# ASIC-Board.net
KiCad netlist of a schematic drawn in Altium Designer
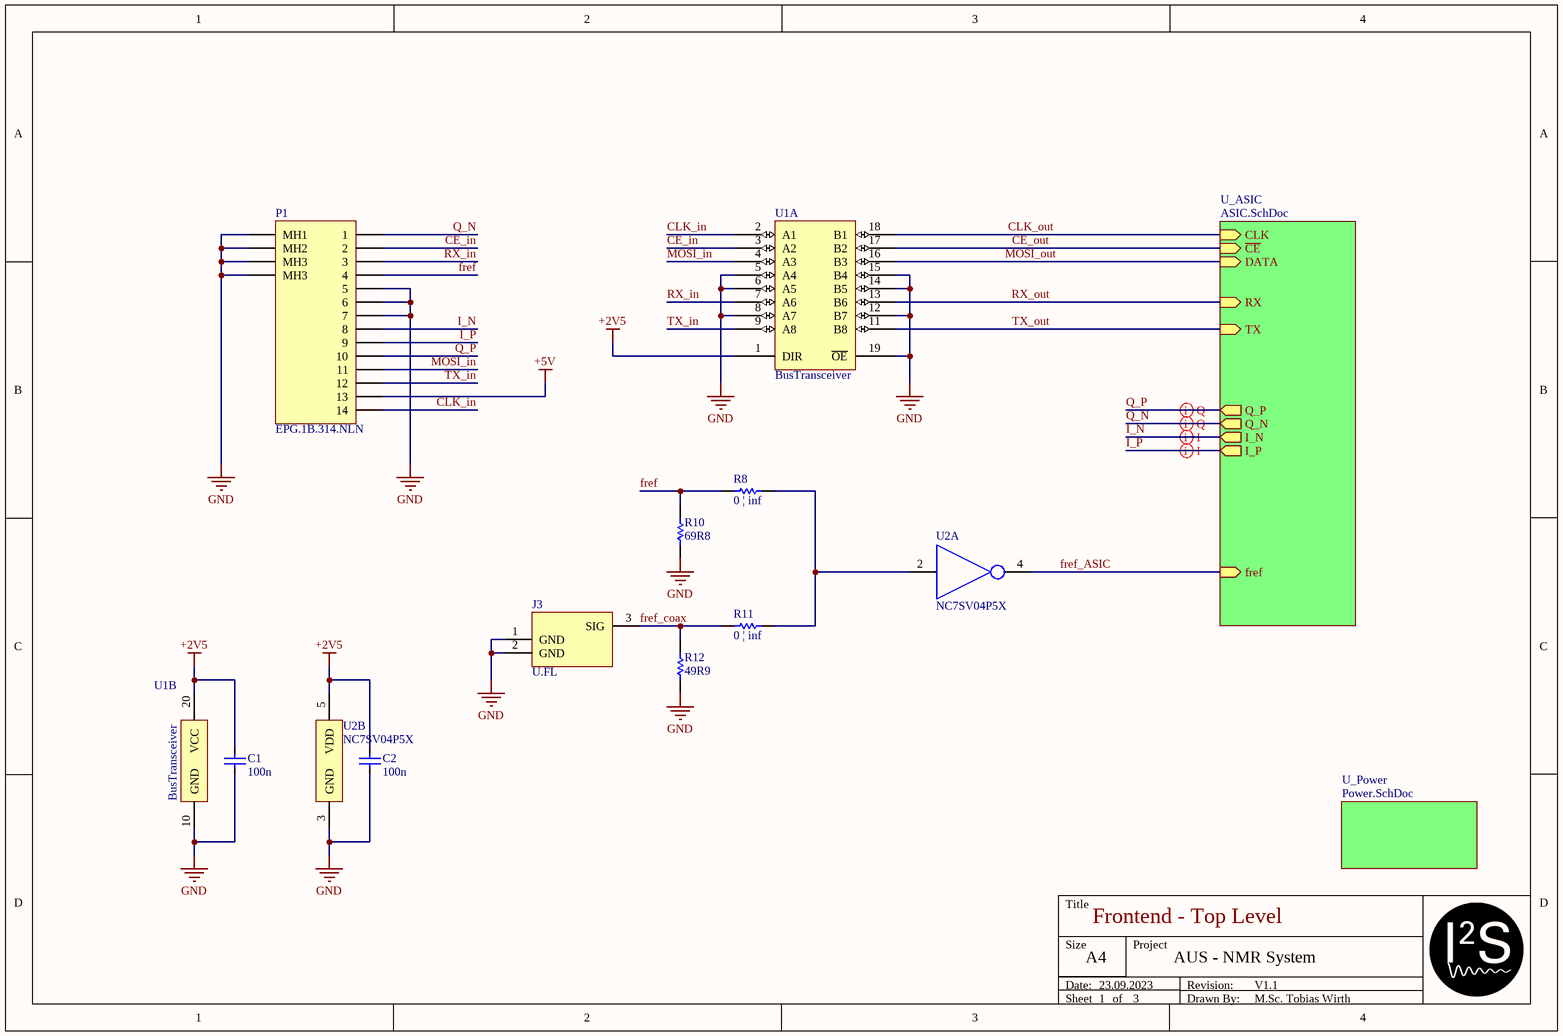
[diagram p0: ASIC-Board.SchDoc]

(export (version "E")
  (design (tool "Eeschema 10.0.6"))
  (components
    (comp (ref "C1") (value "100n") (footprint "CAP_0402") (libsource (lib "IIS-Lib_TW") (part "Cap")))
    (comp (ref "C2") (value "100n") (footprint "CAP_0402") (libsource (lib "IIS-Lib_TW") (part "Cap")))
    (comp (ref "J3") (value "U.FL") (footprint "U.FL") (libsource (lib "IIS-Lib_TW") (part "U.FL")))
    (comp (ref "P1")
      (value "EPG.1B.314.NLN")
      (footprint "EPG.1B.314.NLN")
      (libsource (lib "IIS-Lib_TW") (part "EPG.1B.314.NLN"))
    )
    (comp (ref "R8") (value "0 ¦ inf") (footprint "RES_0402") (libsource (lib "IIS-Lib_TW") (part "Res")))
    (comp (ref "R10") (value "69R8") (footprint "RES_0402") (libsource (lib "IIS-Lib_TW") (part "Res")))
    (comp (ref "R11") (value "0 ¦ inf") (footprint "RES_0402") (libsource (lib "IIS-Lib_TW") (part "Res")))
    (comp (ref "R12") (value "49R9") (footprint "RES_0402") (libsource (lib "IIS-Lib_TW") (part "Res")))
    (comp (ref "U1")
      (value "BusTransceiver")
      (footprint "TSSOP-20")
      (libsource (lib "IIS-Lib_TW") (part "74LVC245A"))
    )
    (comp (ref "U2")
      (value "NC7SV04P5X")
      (footprint "SOT23-65P210X110-5N")
      (libsource (lib "IIS-Lib_TW") (part "NC7SV04P5X"))
    )
  )
  (nets
    (net (code "1") (name "+2V5") (class "Default")
      (node (ref "C1") (pin "1") (pinfunction "1_1") (pintype "passive"))
      (node (ref "C2") (pin "1") (pinfunction "1_1") (pintype "passive"))
      (node (ref "U1") (pin "1") (pinfunction "DIR_1") (pintype "passive"))
      (node (ref "U1") (pin "20") (pinfunction "VCC_20") (pintype "passive"))
      (node (ref "U2") (pin "5") (pinfunction "VDD_5") (pintype "passive"))
    )
    (net (code "2") (name "+5V") (class "Default")
      (node (ref "P1") (pin "13") (pinfunction "13_13") (pintype "passive"))
    )
    (net (code "3") (name "/CE_in") (class "Default")
      (node (ref "P1") (pin "2") (pinfunction "2_2") (pintype "passive"))
      (node (ref "U1") (pin "3") (pinfunction "A2_3") (pintype "bidirectional"))
    )
    (net (code "4") (name "/CE_out") (class "Default")
      (node (ref "U1") (pin "17") (pinfunction "B2_17") (pintype "bidirectional"))
    )
    (net (code "5") (name "/CLK_in") (class "Default")
      (node (ref "P1") (pin "14") (pinfunction "14_14") (pintype "passive"))
      (node (ref "U1") (pin "2") (pinfunction "A1_2") (pintype "bidirectional"))
    )
    (net (code "6") (name "/CLK_out") (class "Default")
      (node (ref "U1") (pin "18") (pinfunction "B1_18") (pintype "bidirectional"))
    )
    (net (code "7") (name "/I_N") (class "Default")
      (node (ref "P1") (pin "8") (pinfunction "8_8") (pintype "passive"))
    )
    (net (code "8") (name "/I_P") (class "Default")
      (node (ref "P1") (pin "9") (pinfunction "9_9") (pintype "passive"))
    )
    (net (code "9") (name "/MOSI_in") (class "Default")
      (node (ref "P1") (pin "11") (pinfunction "11_11") (pintype "passive"))
      (node (ref "U1") (pin "4") (pinfunction "A3_4") (pintype "bidirectional"))
    )
    (net (code "10") (name "/MOSI_out") (class "Default")
      (node (ref "U1") (pin "16") (pinfunction "B3_16") (pintype "bidirectional"))
    )
    (net (code "11") (name "/Q_N") (class "Default")
      (node (ref "P1") (pin "1") (pinfunction "1_1") (pintype "passive"))
    )
    (net (code "12") (name "/Q_P") (class "Default")
      (node (ref "P1") (pin "10") (pinfunction "10_10") (pintype "passive"))
    )
    (net (code "13") (name "/RX_in") (class "Default")
      (node (ref "P1") (pin "3") (pinfunction "3_3") (pintype "passive"))
      (node (ref "U1") (pin "7") (pinfunction "A6_7") (pintype "bidirectional"))
    )
    (net (code "14") (name "/RX_out") (class "Default")
      (node (ref "U1") (pin "13") (pinfunction "B6_13") (pintype "bidirectional"))
    )
    (net (code "15") (name "/TX_in") (class "Default")
      (node (ref "P1") (pin "12") (pinfunction "12_12") (pintype "passive"))
      (node (ref "U1") (pin "9") (pinfunction "A8_9") (pintype "bidirectional"))
    )
    (net (code "16") (name "/TX_out") (class "Default")
      (node (ref "U1") (pin "11") (pinfunction "B8_11") (pintype "bidirectional"))
    )
    (net (code "17") (name "/fref") (class "Default")
      (node (ref "P1") (pin "4") (pinfunction "4_4") (pintype "passive"))
      (node (ref "R10") (pin "2") (pinfunction "2_2") (pintype "passive"))
      (node (ref "R8") (pin "2") (pinfunction "2_2") (pintype "passive"))
    )
    (net (code "18") (name "/fref_ASIC") (class "Default")
      (node (ref "U2") (pin "4") (pinfunction "4_4") (pintype "passive"))
    )
    (net (code "19") (name "/fref_coax") (class "Default")
      (node (ref "J3") (pin "3") (pinfunction "SIG_3") (pintype "passive"))
      (node (ref "R11") (pin "2") (pinfunction "2_2") (pintype "passive"))
      (node (ref "R12") (pin "2") (pinfunction "2_2") (pintype "passive"))
    )
    (net (code "20") (name "GND") (class "Default")
      (node (ref "C1") (pin "2") (pinfunction "2_2") (pintype "passive"))
      (node (ref "C2") (pin "2") (pinfunction "2_2") (pintype "passive"))
      (node (ref "J3") (pin "1") (pinfunction "GND_1") (pintype "passive"))
      (node (ref "J3") (pin "2") (pinfunction "GND_2") (pintype "passive"))
      (node (ref "P1") (pin "15") (pinfunction "MH1_15") (pintype "passive"))
      (node (ref "P1") (pin "16") (pinfunction "MH2_16") (pintype "passive"))
      (node (ref "P1") (pin "17") (pinfunction "MH3_17") (pintype "passive"))
      (node (ref "P1") (pin "18") (pinfunction "MH3_18") (pintype "passive"))
      (node (ref "P1") (pin "5") (pinfunction "5_5") (pintype "passive"))
      (node (ref "P1") (pin "6") (pinfunction "6_6") (pintype "passive"))
      (node (ref "P1") (pin "7") (pinfunction "7_7") (pintype "passive"))
      (node (ref "R10") (pin "1") (pinfunction "1_1") (pintype "passive"))
      (node (ref "R12") (pin "1") (pinfunction "1_1") (pintype "passive"))
      (node (ref "U1") (pin "10") (pinfunction "GND_10") (pintype "passive"))
      (node (ref "U1") (pin "12") (pinfunction "B7_12") (pintype "bidirectional"))
      (node (ref "U1") (pin "14") (pinfunction "B5_14") (pintype "bidirectional"))
      (node (ref "U1") (pin "15") (pinfunction "B4_15") (pintype "bidirectional"))
      (node (ref "U1") (pin "19") (pinfunction "~{OE}_19") (pintype "passive"))
      (node (ref "U1") (pin "5") (pinfunction "A4_5") (pintype "bidirectional"))
      (node (ref "U1") (pin "6") (pinfunction "A5_6") (pintype "bidirectional"))
      (node (ref "U1") (pin "8") (pinfunction "A7_8") (pintype "bidirectional"))
      (node (ref "U2") (pin "3") (pinfunction "GND_3") (pintype "passive"))
    )
    (net (code "21") (name "Net-(R11-Pad1)") (class "Default")
      (node (ref "R11") (pin "1") (pinfunction "1_1") (pintype "passive"))
      (node (ref "R8") (pin "1") (pinfunction "1_1") (pintype "passive"))
      (node (ref "U2") (pin "2") (pinfunction "2_2") (pintype "passive"))
    )
  )
)
